# usb-100basefx.net
KiCad netlist of a schematic drawn in EAGLE
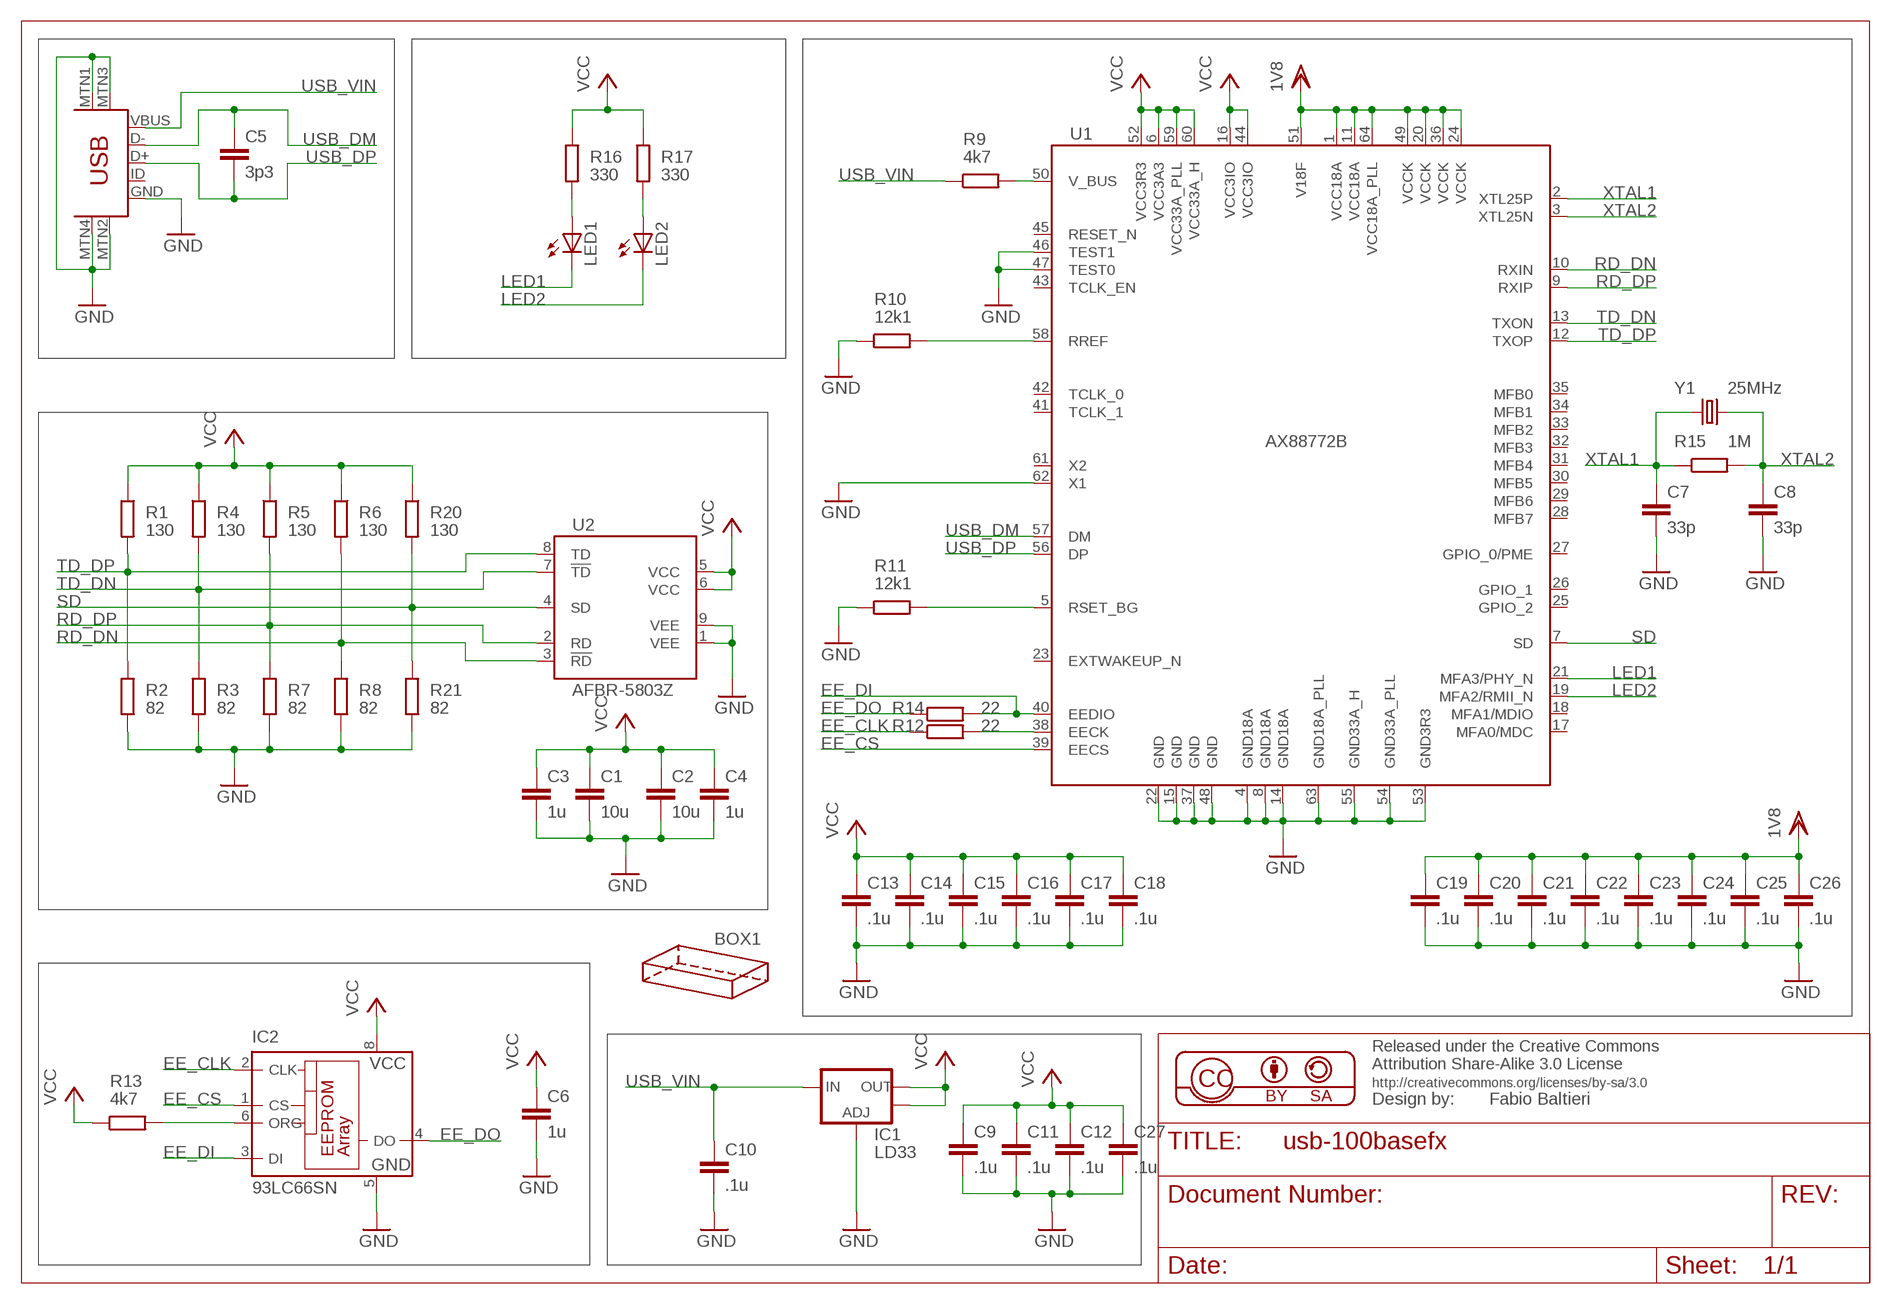
[diagram p0: schematic, sheet 1]

(export (version "E")
  (design (tool "Eeschema 10.0.6"))
  (components
    (comp (ref "BOX1")
      (value "HAMMOND-BOX-R")
      (footprint "eagle-import:1551R")
      (libsource (lib "eagle-import") (part "HAMMOND-BOX-R"))
    )
    (comp (ref "C1")
      (value "10u")
      (footprint "eagle-import:C0603")
      (libsource (lib "eagle-import") (part "C-EUC0603"))
    )
    (comp (ref "C2")
      (value "10u")
      (footprint "eagle-import:C0603")
      (libsource (lib "eagle-import") (part "C-EUC0603"))
    )
    (comp (ref "C3")
      (value "1u")
      (footprint "eagle-import:C0603")
      (libsource (lib "eagle-import") (part "C-EUC0603"))
    )
    (comp (ref "C4")
      (value "1u")
      (footprint "eagle-import:C0603")
      (libsource (lib "eagle-import") (part "C-EUC0603"))
    )
    (comp (ref "C5")
      (value "3p3")
      (footprint "eagle-import:C0603")
      (libsource (lib "eagle-import") (part "C-EUC0603"))
    )
    (comp (ref "C6")
      (value "1u")
      (footprint "eagle-import:C0603")
      (libsource (lib "eagle-import") (part "C-EUC0603"))
    )
    (comp (ref "C7")
      (value "33p")
      (footprint "eagle-import:C0603")
      (libsource (lib "eagle-import") (part "C-EUC0603"))
    )
    (comp (ref "C8")
      (value "33p")
      (footprint "eagle-import:C0603")
      (libsource (lib "eagle-import") (part "C-EUC0603"))
    )
    (comp (ref "C9")
      (value ".1u")
      (footprint "eagle-import:C0603")
      (libsource (lib "eagle-import") (part "C-EUC0603"))
    )
    (comp (ref "C10")
      (value ".1u")
      (footprint "eagle-import:C0603")
      (libsource (lib "eagle-import") (part "C-EUC0603"))
    )
    (comp (ref "C11")
      (value ".1u")
      (footprint "eagle-import:C0603")
      (libsource (lib "eagle-import") (part "C-EUC0603"))
    )
    (comp (ref "C12")
      (value ".1u")
      (footprint "eagle-import:C0603")
      (libsource (lib "eagle-import") (part "C-EUC0603"))
    )
    (comp (ref "C13")
      (value ".1u")
      (footprint "eagle-import:C0603")
      (libsource (lib "eagle-import") (part "C-EUC0603"))
    )
    (comp (ref "C14")
      (value ".1u")
      (footprint "eagle-import:C0603")
      (libsource (lib "eagle-import") (part "C-EUC0603"))
    )
    (comp (ref "C15")
      (value ".1u")
      (footprint "eagle-import:C0603")
      (libsource (lib "eagle-import") (part "C-EUC0603"))
    )
    (comp (ref "C16")
      (value ".1u")
      (footprint "eagle-import:C0603")
      (libsource (lib "eagle-import") (part "C-EUC0603"))
    )
    (comp (ref "C17")
      (value ".1u")
      (footprint "eagle-import:C0603")
      (libsource (lib "eagle-import") (part "C-EUC0603"))
    )
    (comp (ref "C18")
      (value ".1u")
      (footprint "eagle-import:C0603")
      (libsource (lib "eagle-import") (part "C-EUC0603"))
    )
    (comp (ref "C19")
      (value ".1u")
      (footprint "eagle-import:C0603")
      (libsource (lib "eagle-import") (part "C-EUC0603"))
    )
    (comp (ref "C20")
      (value ".1u")
      (footprint "eagle-import:C0603")
      (libsource (lib "eagle-import") (part "C-EUC0603"))
    )
    (comp (ref "C21")
      (value ".1u")
      (footprint "eagle-import:C0603")
      (libsource (lib "eagle-import") (part "C-EUC0603"))
    )
    (comp (ref "C22")
      (value ".1u")
      (footprint "eagle-import:C0603")
      (libsource (lib "eagle-import") (part "C-EUC0603"))
    )
    (comp (ref "C23")
      (value ".1u")
      (footprint "eagle-import:C0603")
      (libsource (lib "eagle-import") (part "C-EUC0603"))
    )
    (comp (ref "C24")
      (value ".1u")
      (footprint "eagle-import:C0603")
      (libsource (lib "eagle-import") (part "C-EUC0603"))
    )
    (comp (ref "C25")
      (value ".1u")
      (footprint "eagle-import:C0603")
      (libsource (lib "eagle-import") (part "C-EUC0603"))
    )
    (comp (ref "C26")
      (value ".1u")
      (footprint "eagle-import:C0603")
      (libsource (lib "eagle-import") (part "C-EUC0603"))
    )
    (comp (ref "C27")
      (value ".1u")
      (footprint "eagle-import:C0603")
      (libsource (lib "eagle-import") (part "C-EUC0603"))
    )
    (comp (ref "IC1")
      (value "LD33")
      (footprint "eagle-import:SOT223")
      (libsource (lib "eagle-import") (part "V_REG_LM1117SOT223"))
    )
    (comp (ref "IC2")
      (value "93LC66SN")
      (footprint "eagle-import:SO-08")
      (fields (field (name "MF") "MICROCHIP") (field (name "MPN") "93LC66/SN"))
      (libsource (lib "eagle-import") (part "93SNLC66"))
    )
    (comp (ref "LED1")
      (value "LEDCHIPLED_0805")
      (footprint "eagle-import:CHIPLED_0805")
      (libsource (lib "eagle-import") (part "LEDCHIPLED_0805"))
    )
    (comp (ref "LED2")
      (value "LEDCHIPLED_0805")
      (footprint "eagle-import:CHIPLED_0805")
      (libsource (lib "eagle-import") (part "LEDCHIPLED_0805"))
    )
    (comp (ref "R1")
      (value "130")
      (footprint "eagle-import:R0603")
      (libsource (lib "eagle-import") (part "R-EU_R0603"))
    )
    (comp (ref "R2")
      (value "82")
      (footprint "eagle-import:R0603")
      (libsource (lib "eagle-import") (part "R-EU_R0603"))
    )
    (comp (ref "R3")
      (value "82")
      (footprint "eagle-import:R0603")
      (libsource (lib "eagle-import") (part "R-EU_R0603"))
    )
    (comp (ref "R4")
      (value "130")
      (footprint "eagle-import:R0603")
      (libsource (lib "eagle-import") (part "R-EU_R0603"))
    )
    (comp (ref "R5")
      (value "130")
      (footprint "eagle-import:R0603")
      (libsource (lib "eagle-import") (part "R-EU_R0603"))
    )
    (comp (ref "R6")
      (value "130")
      (footprint "eagle-import:R0603")
      (libsource (lib "eagle-import") (part "R-EU_R0603"))
    )
    (comp (ref "R7")
      (value "82")
      (footprint "eagle-import:R0603")
      (libsource (lib "eagle-import") (part "R-EU_R0603"))
    )
    (comp (ref "R8")
      (value "82")
      (footprint "eagle-import:R0603")
      (libsource (lib "eagle-import") (part "R-EU_R0603"))
    )
    (comp (ref "R9")
      (value "4k7")
      (footprint "eagle-import:R0603")
      (libsource (lib "eagle-import") (part "R-EU_R0603"))
    )
    (comp (ref "R10")
      (value "12k1")
      (footprint "eagle-import:R0603")
      (libsource (lib "eagle-import") (part "R-EU_R0603"))
    )
    (comp (ref "R11")
      (value "12k1")
      (footprint "eagle-import:R0603")
      (libsource (lib "eagle-import") (part "R-EU_R0603"))
    )
    (comp (ref "R12")
      (value "22")
      (footprint "eagle-import:R0603")
      (libsource (lib "eagle-import") (part "R-EU_R0603"))
    )
    (comp (ref "R13")
      (value "4k7")
      (footprint "eagle-import:R0603")
      (libsource (lib "eagle-import") (part "R-EU_R0603"))
    )
    (comp (ref "R14")
      (value "22")
      (footprint "eagle-import:R0603")
      (libsource (lib "eagle-import") (part "R-EU_R0603"))
    )
    (comp (ref "R15")
      (value "1M")
      (footprint "eagle-import:R0603")
      (libsource (lib "eagle-import") (part "R-EU_R0603"))
    )
    (comp (ref "R16")
      (value "330")
      (footprint "eagle-import:R0603")
      (libsource (lib "eagle-import") (part "R-EU_R0603"))
    )
    (comp (ref "R17")
      (value "330")
      (footprint "eagle-import:R0603")
      (libsource (lib "eagle-import") (part "R-EU_R0603"))
    )
    (comp (ref "R20")
      (value "130")
      (footprint "eagle-import:R0603")
      (libsource (lib "eagle-import") (part "R-EU_R0603"))
    )
    (comp (ref "R21")
      (value "82")
      (footprint "eagle-import:R0603")
      (libsource (lib "eagle-import") (part "R-EU_R0603"))
    )
    (comp (ref "U$1")
      (value "USB-MINIB-5PIN")
      (footprint "eagle-import:USB-MINIB")
      (libsource (lib "eagle-import") (part "USB-MINIB-5PIN"))
    )
    (comp (ref "U1")
      (value "AX88772B")
      (footprint "eagle-import:LQFP64-0.4MM")
      (libsource (lib "eagle-import") (part "AX88772B"))
    )
    (comp (ref "U2")
      (value "AFBR-5803Z")
      (footprint "eagle-import:AFBR-5803Z")
      (libsource (lib "eagle-import") (part "AFBR-5803Z"))
    )
    (comp (ref "Y1")
      (value "25MHz")
      (footprint "eagle-import:CRYSTAL-SMD-5X3")
      (libsource (lib "eagle-import") (part "CRYSTAL5X3"))
    )
  )
  (nets
    (net (code "1") (name "/EE_CLK") (class "Default")
      (node (ref "IC2") (pin "2") (pinfunction "CLK_2") (pintype "input"))
      (node (ref "R12") (pin "1") (pinfunction "1_1") (pintype "passive"))
    )
    (net (code "2") (name "/EE_CS") (class "Default")
      (node (ref "IC2") (pin "1") (pinfunction "CS_1") (pintype "input"))
      (node (ref "U1") (pin "39") (pinfunction "EECS_39") (pintype "bidirectional"))
    )
    (net (code "3") (name "/EE_DI") (class "Default")
      (node (ref "IC2") (pin "3") (pinfunction "DI_3") (pintype "input"))
      (node (ref "R14") (pin "2") (pinfunction "2_2") (pintype "passive"))
      (node (ref "U1") (pin "40") (pinfunction "EEDIO_40") (pintype "bidirectional"))
    )
    (net (code "4") (name "/EE_DO") (class "Default")
      (node (ref "IC2") (pin "4") (pinfunction "DO_4") (pintype "tri_state"))
      (node (ref "R14") (pin "1") (pinfunction "1_1") (pintype "passive"))
    )
    (net (code "5") (name "/LED1") (class "Default")
      (node (ref "LED1") (pin "C") (pinfunction "C_C") (pintype "passive"))
      (node (ref "U1") (pin "21") (pinfunction "MFA3/PHY_N_21") (pintype "bidirectional"))
    )
    (net (code "6") (name "/LED2") (class "Default")
      (node (ref "LED2") (pin "C") (pinfunction "C_C") (pintype "passive"))
      (node (ref "U1") (pin "19") (pinfunction "MFA2/RMII_N_19") (pintype "bidirectional"))
    )
    (net (code "7") (name "/RD_DN") (class "Default")
      (node (ref "R6") (pin "2") (pinfunction "2_2") (pintype "passive"))
      (node (ref "R8") (pin "1") (pinfunction "1_1") (pintype "passive"))
      (node (ref "U1") (pin "10") (pinfunction "RXIN_10") (pintype "bidirectional"))
      (node (ref "U2") (pin "3") (pinfunction "~{RD}_3") (pintype "bidirectional"))
    )
    (net (code "8") (name "/RD_DP") (class "Default")
      (node (ref "R5") (pin "2") (pinfunction "2_2") (pintype "passive"))
      (node (ref "R7") (pin "1") (pinfunction "1_1") (pintype "passive"))
      (node (ref "U1") (pin "9") (pinfunction "RXIP_9") (pintype "bidirectional"))
      (node (ref "U2") (pin "2") (pinfunction "RD_2") (pintype "bidirectional"))
    )
    (net (code "9") (name "/SD") (class "Default")
      (node (ref "R20") (pin "2") (pinfunction "2_2") (pintype "passive"))
      (node (ref "R21") (pin "1") (pinfunction "1_1") (pintype "passive"))
      (node (ref "U1") (pin "7") (pinfunction "SD_7") (pintype "bidirectional"))
      (node (ref "U2") (pin "4") (pinfunction "SD_4") (pintype "bidirectional"))
    )
    (net (code "10") (name "/TD_DN") (class "Default")
      (node (ref "R3") (pin "1") (pinfunction "1_1") (pintype "passive"))
      (node (ref "R4") (pin "2") (pinfunction "2_2") (pintype "passive"))
      (node (ref "U1") (pin "13") (pinfunction "TXON_13") (pintype "bidirectional"))
      (node (ref "U2") (pin "7") (pinfunction "~{TD}_7") (pintype "bidirectional"))
    )
    (net (code "11") (name "/TD_DP") (class "Default")
      (node (ref "R1") (pin "2") (pinfunction "2_2") (pintype "passive"))
      (node (ref "R2") (pin "1") (pinfunction "1_1") (pintype "passive"))
      (node (ref "U1") (pin "12") (pinfunction "TXOP_12") (pintype "bidirectional"))
      (node (ref "U2") (pin "8") (pinfunction "TD_8") (pintype "bidirectional"))
    )
    (net (code "12") (name "/USB_DM") (class "Default")
      (node (ref "C5") (pin "1") (pinfunction "1_1") (pintype "passive"))
      (node (ref "U$1") (pin "D-") (pinfunction "D-_D-") (pintype "bidirectional"))
      (node (ref "U1") (pin "57") (pinfunction "DM_57") (pintype "bidirectional"))
    )
    (net (code "13") (name "/USB_DP") (class "Default")
      (node (ref "C5") (pin "2") (pinfunction "2_2") (pintype "passive"))
      (node (ref "U$1") (pin "D+") (pinfunction "D+_D+") (pintype "bidirectional"))
      (node (ref "U1") (pin "56") (pinfunction "DP_56") (pintype "bidirectional"))
    )
    (net (code "14") (name "/USB_VIN") (class "Default")
      (node (ref "C10") (pin "1") (pinfunction "1_1") (pintype "passive"))
      (node (ref "IC1") (pin "3") (pinfunction "IN_3") (pintype "input"))
      (node (ref "R9") (pin "1") (pinfunction "1_1") (pintype "passive"))
      (node (ref "U$1") (pin "VBUS") (pinfunction "VBUS_VBUS") (pintype "bidirectional"))
    )
    (net (code "15") (name "/XTAL1") (class "Default")
      (node (ref "C7") (pin "1") (pinfunction "1_1") (pintype "passive"))
      (node (ref "R15") (pin "1") (pinfunction "1_1") (pintype "passive"))
      (node (ref "U1") (pin "2") (pinfunction "XTL25P_2") (pintype "bidirectional"))
      (node (ref "Y1") (pin "1") (pinfunction "1_1") (pintype "passive"))
    )
    (net (code "16") (name "/XTAL2") (class "Default")
      (node (ref "C8") (pin "1") (pinfunction "1_1") (pintype "passive"))
      (node (ref "R15") (pin "2") (pinfunction "2_2") (pintype "passive"))
      (node (ref "U1") (pin "3") (pinfunction "XTL25N_3") (pintype "bidirectional"))
      (node (ref "Y1") (pin "3") (pinfunction "2_3") (pintype "passive"))
    )
    (net (code "17") (name "1V8") (class "Default")
      (node (ref "C19") (pin "1") (pinfunction "1_1") (pintype "passive"))
      (node (ref "C20") (pin "1") (pinfunction "1_1") (pintype "passive"))
      (node (ref "C21") (pin "1") (pinfunction "1_1") (pintype "passive"))
      (node (ref "C22") (pin "1") (pinfunction "1_1") (pintype "passive"))
      (node (ref "C23") (pin "1") (pinfunction "1_1") (pintype "passive"))
      (node (ref "C24") (pin "1") (pinfunction "1_1") (pintype "passive"))
      (node (ref "C25") (pin "1") (pinfunction "1_1") (pintype "passive"))
      (node (ref "C26") (pin "1") (pinfunction "1_1") (pintype "passive"))
      (node (ref "U1") (pin "1") (pinfunction "VCC18A_1") (pintype "bidirectional"))
      (node (ref "U1") (pin "11") (pinfunction "VCC18A_11") (pintype "bidirectional"))
      (node (ref "U1") (pin "20") (pinfunction "VCCK_20") (pintype "bidirectional"))
      (node (ref "U1") (pin "24") (pinfunction "VCCK_24") (pintype "bidirectional"))
      (node (ref "U1") (pin "36") (pinfunction "VCCK_36") (pintype "bidirectional"))
      (node (ref "U1") (pin "49") (pinfunction "VCCK_49") (pintype "bidirectional"))
      (node (ref "U1") (pin "51") (pinfunction "V18F_51") (pintype "bidirectional"))
      (node (ref "U1") (pin "64") (pinfunction "VCC18A_PLL_64") (pintype "bidirectional"))
    )
    (net (code "18") (name "GND") (class "Default")
      (node (ref "C1") (pin "2") (pinfunction "2_2") (pintype "passive"))
      (node (ref "C10") (pin "2") (pinfunction "2_2") (pintype "passive"))
      (node (ref "C11") (pin "2") (pinfunction "2_2") (pintype "passive"))
      (node (ref "C12") (pin "2") (pinfunction "2_2") (pintype "passive"))
      (node (ref "C13") (pin "2") (pinfunction "2_2") (pintype "passive"))
      (node (ref "C14") (pin "2") (pinfunction "2_2") (pintype "passive"))
      (node (ref "C15") (pin "2") (pinfunction "2_2") (pintype "passive"))
      (node (ref "C16") (pin "2") (pinfunction "2_2") (pintype "passive"))
      (node (ref "C17") (pin "2") (pinfunction "2_2") (pintype "passive"))
      (node (ref "C18") (pin "2") (pinfunction "2_2") (pintype "passive"))
      (node (ref "C19") (pin "2") (pinfunction "2_2") (pintype "passive"))
      (node (ref "C2") (pin "2") (pinfunction "2_2") (pintype "passive"))
      (node (ref "C20") (pin "2") (pinfunction "2_2") (pintype "passive"))
      (node (ref "C21") (pin "2") (pinfunction "2_2") (pintype "passive"))
      (node (ref "C22") (pin "2") (pinfunction "2_2") (pintype "passive"))
      (node (ref "C23") (pin "2") (pinfunction "2_2") (pintype "passive"))
      (node (ref "C24") (pin "2") (pinfunction "2_2") (pintype "passive"))
      (node (ref "C25") (pin "2") (pinfunction "2_2") (pintype "passive"))
      (node (ref "C26") (pin "2") (pinfunction "2_2") (pintype "passive"))
      (node (ref "C27") (pin "2") (pinfunction "2_2") (pintype "passive"))
      (node (ref "C3") (pin "2") (pinfunction "2_2") (pintype "passive"))
      (node (ref "C4") (pin "2") (pinfunction "2_2") (pintype "passive"))
      (node (ref "C6") (pin "2") (pinfunction "2_2") (pintype "passive"))
      (node (ref "C7") (pin "2") (pinfunction "2_2") (pintype "passive"))
      (node (ref "C8") (pin "2") (pinfunction "2_2") (pintype "passive"))
      (node (ref "C9") (pin "2") (pinfunction "2_2") (pintype "passive"))
      (node (ref "IC1") (pin "1") (pinfunction "ADJ_1") (pintype "input"))
      (node (ref "IC2") (pin "5") (pinfunction "GND_5") (pintype "power_in"))
      (node (ref "R10") (pin "1") (pinfunction "1_1") (pintype "passive"))
      (node (ref "R11") (pin "1") (pinfunction "1_1") (pintype "passive"))
      (node (ref "R2") (pin "2") (pinfunction "2_2") (pintype "passive"))
      (node (ref "R21") (pin "2") (pinfunction "2_2") (pintype "passive"))
      (node (ref "R3") (pin "2") (pinfunction "2_2") (pintype "passive"))
      (node (ref "R7") (pin "2") (pinfunction "2_2") (pintype "passive"))
      (node (ref "R8") (pin "2") (pinfunction "2_2") (pintype "passive"))
      (node (ref "U$1") (pin "GND") (pinfunction "GND_GND") (pintype "bidirectional"))
      (node (ref "U$1") (pin "MTN1") (pinfunction "MTN2_MTN1") (pintype "bidirectional"))
      (node (ref "U$1") (pin "MTN2") (pinfunction "MTN3_MTN2") (pintype "bidirectional"))
      (node (ref "U$1") (pin "MTN3") (pinfunction "MTN1_MTN3") (pintype "bidirectional"))
      (node (ref "U$1") (pin "MTN4") (pinfunction "MTN4_MTN4") (pintype "bidirectional"))
      (node (ref "U1") (pin "14") (pinfunction "GND18A_14") (pintype "bidirectional"))
      (node (ref "U1") (pin "15") (pinfunction "GND_15") (pintype "bidirectional"))
      (node (ref "U1") (pin "22") (pinfunction "GND_22") (pintype "bidirectional"))
      (node (ref "U1") (pin "37") (pinfunction "GND_37") (pintype "bidirectional"))
      (node (ref "U1") (pin "4") (pinfunction "GND18A_4") (pintype "bidirectional"))
      (node (ref "U1") (pin "46") (pinfunction "TEST1_46") (pintype "bidirectional"))
      (node (ref "U1") (pin "47") (pinfunction "TEST0_47") (pintype "bidirectional"))
      (node (ref "U1") (pin "48") (pinfunction "GND_48") (pintype "bidirectional"))
      (node (ref "U1") (pin "53") (pinfunction "GND3R3_53") (pintype "bidirectional"))
      (node (ref "U1") (pin "54") (pinfunction "GND33A_PLL_54") (pintype "bidirectional"))
      (node (ref "U1") (pin "55") (pinfunction "GND33A_H_55") (pintype "bidirectional"))
      (node (ref "U1") (pin "62") (pinfunction "X1_62") (pintype "bidirectional"))
      (node (ref "U1") (pin "63") (pinfunction "GND18A_PLL_63") (pintype "bidirectional"))
      (node (ref "U1") (pin "8") (pinfunction "GND18A_8") (pintype "bidirectional"))
      (node (ref "U2") (pin "1") (pinfunction "VEE_1") (pintype "bidirectional"))
      (node (ref "U2") (pin "9") (pinfunction "VEE_9") (pintype "bidirectional"))
    )
    (net (code "19") (name "Net-(IC2-ORG)") (class "Default")
      (node (ref "IC2") (pin "6") (pinfunction "ORG_6") (pintype "input"))
      (node (ref "R13") (pin "2") (pinfunction "2_2") (pintype "passive"))
    )
    (net (code "20") (name "Net-(LED1-PadA)") (class "Default")
      (node (ref "LED1") (pin "A") (pinfunction "A_A") (pintype "passive"))
      (node (ref "R16") (pin "2") (pinfunction "2_2") (pintype "passive"))
    )
    (net (code "21") (name "Net-(LED2-PadA)") (class "Default")
      (node (ref "LED2") (pin "A") (pinfunction "A_A") (pintype "passive"))
      (node (ref "R17") (pin "2") (pinfunction "2_2") (pintype "passive"))
    )
    (net (code "22") (name "Net-(U1-EECK)") (class "Default")
      (node (ref "R12") (pin "2") (pinfunction "2_2") (pintype "passive"))
      (node (ref "U1") (pin "38") (pinfunction "EECK_38") (pintype "bidirectional"))
    )
    (net (code "23") (name "Net-(U1-RREF)") (class "Default")
      (node (ref "R10") (pin "2") (pinfunction "2_2") (pintype "passive"))
      (node (ref "U1") (pin "58") (pinfunction "RREF_58") (pintype "bidirectional"))
    )
    (net (code "24") (name "Net-(U1-RSET_BG)") (class "Default")
      (node (ref "R11") (pin "2") (pinfunction "2_2") (pintype "passive"))
      (node (ref "U1") (pin "5") (pinfunction "RSET_BG_5") (pintype "bidirectional"))
    )
    (net (code "25") (name "Net-(U1-V_BUS)") (class "Default")
      (node (ref "R9") (pin "2") (pinfunction "2_2") (pintype "passive"))
      (node (ref "U1") (pin "50") (pinfunction "V_BUS_50") (pintype "bidirectional"))
    )
    (net (code "26") (name "VCC") (class "Default")
      (node (ref "C1") (pin "1") (pinfunction "1_1") (pintype "passive"))
      (node (ref "C11") (pin "1") (pinfunction "1_1") (pintype "passive"))
      (node (ref "C12") (pin "1") (pinfunction "1_1") (pintype "passive"))
      (node (ref "C13") (pin "1") (pinfunction "1_1") (pintype "passive"))
      (node (ref "C14") (pin "1") (pinfunction "1_1") (pintype "passive"))
      (node (ref "C15") (pin "1") (pinfunction "1_1") (pintype "passive"))
      (node (ref "C16") (pin "1") (pinfunction "1_1") (pintype "passive"))
      (node (ref "C17") (pin "1") (pinfunction "1_1") (pintype "passive"))
      (node (ref "C18") (pin "1") (pinfunction "1_1") (pintype "passive"))
      (node (ref "C2") (pin "1") (pinfunction "1_1") (pintype "passive"))
      (node (ref "C27") (pin "1") (pinfunction "1_1") (pintype "passive"))
      (node (ref "C3") (pin "1") (pinfunction "1_1") (pintype "passive"))
      (node (ref "C4") (pin "1") (pinfunction "1_1") (pintype "passive"))
      (node (ref "C6") (pin "1") (pinfunction "1_1") (pintype "passive"))
      (node (ref "C9") (pin "1") (pinfunction "1_1") (pintype "passive"))
      (node (ref "IC1") (pin "2") (pinfunction "OUT_2") (pintype "output"))
      (node (ref "IC1") (pin "4") (pinfunction "OUT_4") (pintype "output"))
      (node (ref "IC2") (pin "8") (pinfunction "VCC_8") (pintype "power_in"))
      (node (ref "R1") (pin "1") (pinfunction "1_1") (pintype "passive"))
      (node (ref "R13") (pin "1") (pinfunction "1_1") (pintype "passive"))
      (node (ref "R16") (pin "1") (pinfunction "1_1") (pintype "passive"))
      (node (ref "R17") (pin "1") (pinfunction "1_1") (pintype "passive"))
      (node (ref "R20") (pin "1") (pinfunction "1_1") (pintype "passive"))
      (node (ref "R4") (pin "1") (pinfunction "1_1") (pintype "passive"))
      (node (ref "R5") (pin "1") (pinfunction "1_1") (pintype "passive"))
      (node (ref "R6") (pin "1") (pinfunction "1_1") (pintype "passive"))
      (node (ref "U1") (pin "16") (pinfunction "VCC3IO_16") (pintype "bidirectional"))
      (node (ref "U1") (pin "44") (pinfunction "VCC3IO_44") (pintype "bidirectional"))
      (node (ref "U1") (pin "52") (pinfunction "VCC3R3_52") (pintype "bidirectional"))
      (node (ref "U1") (pin "59") (pinfunction "VCC33A_PLL_59") (pintype "bidirectional"))
      (node (ref "U1") (pin "6") (pinfunction "VCC3A3_6") (pintype "bidirectional"))
      (node (ref "U1") (pin "60") (pinfunction "VCC33A_H_60") (pintype "bidirectional"))
      (node (ref "U2") (pin "5") (pinfunction "VCC_5") (pintype "bidirectional"))
      (node (ref "U2") (pin "6") (pinfunction "VCC_6") (pintype "bidirectional"))
    )
    (net (code "27") (name "unconnected-(IC2-NU-Pad7)") (class "Default")
      (node (ref "IC2") (pin "7") (pinfunction "NU_7") (pintype "passive"))
    )
    (net (code "28") (name "unconnected-(U$1-PadID)") (class "Default")
      (node (ref "U$1") (pin "ID") (pinfunction "ID_ID") (pintype "bidirectional"))
    )
    (net (code "29") (name "unconnected-(U1-EXTWAKEUP_N-Pad23)") (class "Default")
      (node (ref "U1") (pin "23") (pinfunction "EXTWAKEUP_N_23") (pintype "bidirectional"))
    )
    (net (code "30") (name "unconnected-(U1-GPIO_0{slash}PME-Pad27)") (class "Default")
      (node (ref "U1") (pin "27") (pinfunction "GPIO_0/PME_27") (pintype "bidirectional"))
    )
    (net (code "31") (name "unconnected-(U1-GPIO_1-Pad26)") (class "Default")
      (node (ref "U1") (pin "26") (pinfunction "GPIO_1_26") (pintype "bidirectional"))
    )
    (net (code "32") (name "unconnected-(U1-GPIO_2-Pad25)") (class "Default")
      (node (ref "U1") (pin "25") (pinfunction "GPIO_2_25") (pintype "bidirectional"))
    )
    (net (code "33") (name "unconnected-(U1-MFA0{slash}MDC-Pad17)") (class "Default")
      (node (ref "U1") (pin "17") (pinfunction "MFA0/MDC_17") (pintype "bidirectional"))
    )
    (net (code "34") (name "unconnected-(U1-MFA1{slash}MDIO-Pad18)") (class "Default")
      (node (ref "U1") (pin "18") (pinfunction "MFA1/MDIO_18") (pintype "bidirectional"))
    )
    (net (code "35") (name "unconnected-(U1-MFB0-Pad35)") (class "Default")
      (node (ref "U1") (pin "35") (pinfunction "MFB0_35") (pintype "bidirectional"))
    )
    (net (code "36") (name "unconnected-(U1-MFB1-Pad34)") (class "Default")
      (node (ref "U1") (pin "34") (pinfunction "MFB1_34") (pintype "bidirectional"))
    )
    (net (code "37") (name "unconnected-(U1-MFB2-Pad33)") (class "Default")
      (node (ref "U1") (pin "33") (pinfunction "MFB2_33") (pintype "bidirectional"))
    )
    (net (code "38") (name "unconnected-(U1-MFB3-Pad32)") (class "Default")
      (node (ref "U1") (pin "32") (pinfunction "MFB3_32") (pintype "bidirectional"))
    )
    (net (code "39") (name "unconnected-(U1-MFB4-Pad31)") (class "Default")
      (node (ref "U1") (pin "31") (pinfunction "MFB4_31") (pintype "bidirectional"))
    )
    (net (code "40") (name "unconnected-(U1-MFB5-Pad30)") (class "Default")
      (node (ref "U1") (pin "30") (pinfunction "MFB5_30") (pintype "bidirectional"))
    )
    (net (code "41") (name "unconnected-(U1-MFB6-Pad29)") (class "Default")
      (node (ref "U1") (pin "29") (pinfunction "MFB6_29") (pintype "bidirectional"))
    )
    (net (code "42") (name "unconnected-(U1-MFB7-Pad28)") (class "Default")
      (node (ref "U1") (pin "28") (pinfunction "MFB7_28") (pintype "bidirectional"))
    )
    (net (code "43") (name "unconnected-(U1-RESET_N-Pad45)") (class "Default")
      (node (ref "U1") (pin "45") (pinfunction "RESET_N_45") (pintype "bidirectional"))
    )
    (net (code "44") (name "unconnected-(U1-TCLK_0-Pad42)") (class "Default")
      (node (ref "U1") (pin "42") (pinfunction "TCLK_0_42") (pintype "bidirectional"))
    )
    (net (code "45") (name "unconnected-(U1-TCLK_1-Pad41)") (class "Default")
      (node (ref "U1") (pin "41") (pinfunction "TCLK_1_41") (pintype "bidirectional"))
    )
    (net (code "46") (name "unconnected-(U1-TCLK_EN-Pad43)") (class "Default")
      (node (ref "U1") (pin "43") (pinfunction "TCLK_EN_43") (pintype "bidirectional"))
    )
    (net (code "47") (name "unconnected-(U1-X2-Pad61)") (class "Default")
      (node (ref "U1") (pin "61") (pinfunction "X2_61") (pintype "bidirectional"))
    )
  )
)
